# Main.net
KiCad netlist of a schematic drawn in Altium Designer
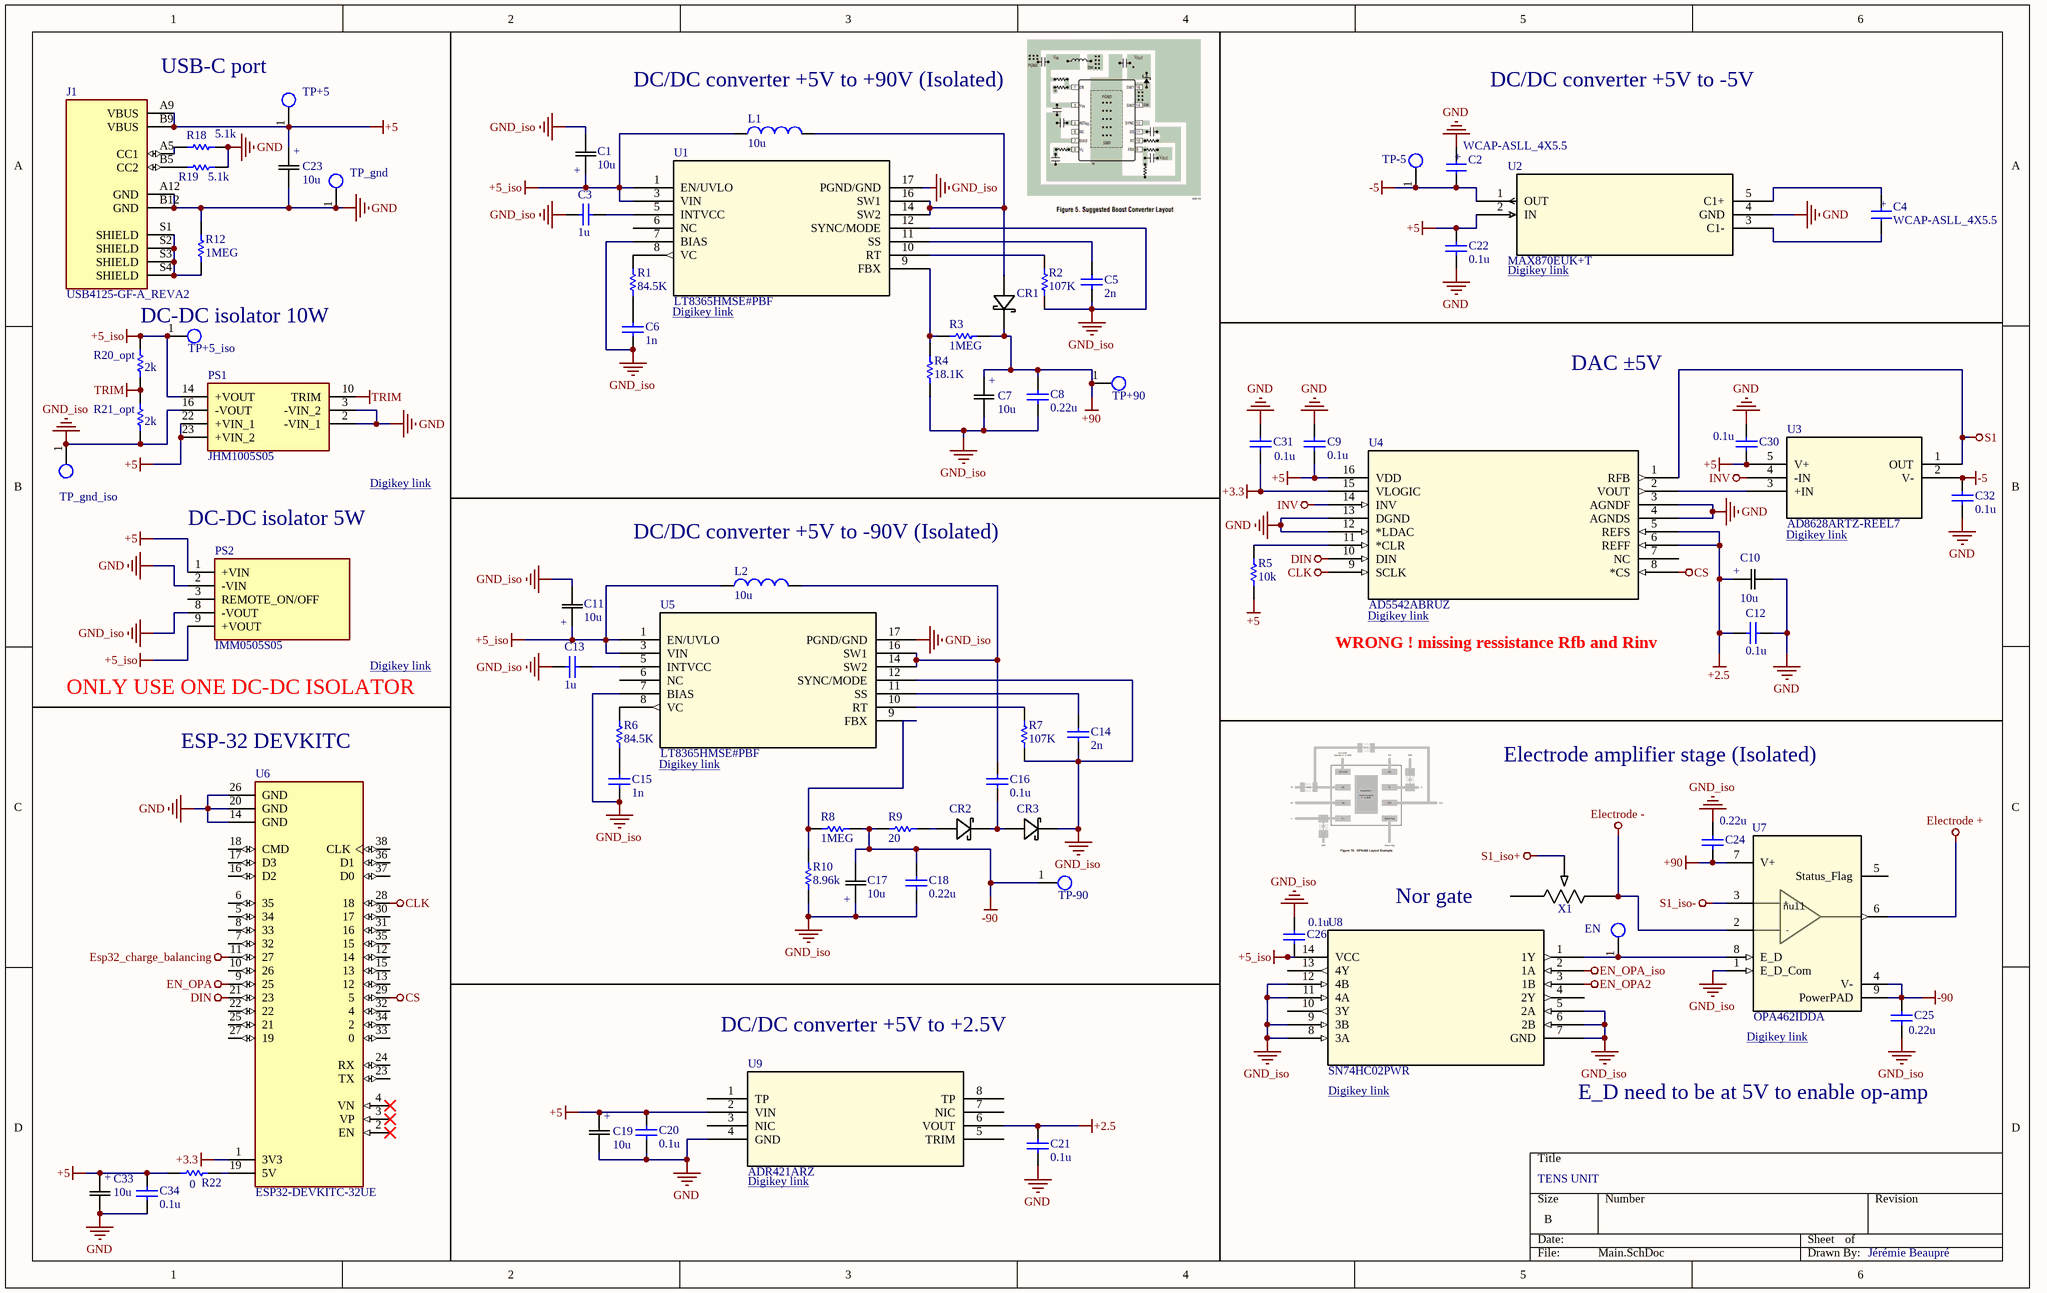
[diagram p0: Main.SchDoc]

(export (version "E")
  (design (tool "Eeschema 10.0.6"))
  (components
    (comp (ref "C1")
      (value "10u")
      (footprint "CAP_BX_10x20_RUB")
      (description "No Description Available")
      (fields
        (field (name "MANUFACTURER_PART_NUMBER") "450BXC10MEFC10X20")
        (field (name "COPYRIGHT") "Copyright (C) 2026 Ultra Librarian. All rights reserved.")
      )
      (libsource (lib "450BXC10MEFC10X20") (part "450BXC10MEFC10X20"))
    )
    (comp (ref "C2")
      (value "WCAP-ASLL_4X5.5")
      (footprint "WCAP-ASLL_4X5.5(DXL)")
      (fields
        (field (name "MF") "{'manufacturer': u'~{W}xfcrth Elektronik'}")
        (field (name "MP") "865060640001")
      )
      (libsource (lib "WCAP-ASLL_4X5.5") (part "WCAP-ASLL_4X5.5"))
    )
    (comp (ref "C3")
      (value "1u")
      (footprint "0805_AVX")
      (description "Capacitor")
      (libsource (lib "Simulation Generic Components") (part "Capacitor"))
    )
    (comp (ref "C4")
      (value "WCAP-ASLL_4X5.5")
      (footprint "WCAP-ASLL_4X5.5(DXL)")
      (fields
        (field (name "MF") "{'manufacturer': u'~{W}xfcrth Elektronik'}")
        (field (name "MP") "865060640001")
      )
      (libsource (lib "WCAP-ASLL_4X5.5") (part "WCAP-ASLL_4X5.5"))
    )
    (comp (ref "C5")
      (value "2n")
      (footprint "CAPC2012X75N")
      (description "Capacitor")
      (libsource (lib "Simulation Generic Components") (part "Capacitor"))
    )
    (comp (ref "C6")
      (value "1n")
      (footprint "CC0805N_YAG")
      (description "Capacitor")
      (libsource (lib "Simulation Generic Components") (part "Capacitor"))
    )
    (comp (ref "C7")
      (value "10u")
      (footprint "CAP_BX_10x20_RUB")
      (description "No Description Available")
      (fields
        (field (name "MANUFACTURER_PART_NUMBER") "450BXC10MEFC10X20")
        (field (name "COPYRIGHT") "Copyright (C) 2026 Ultra Librarian. All rights reserved.")
      )
      (libsource (lib "450BXC10MEFC10X20") (part "450BXC10MEFC10X20"))
    )
    (comp (ref "C8")
      (value "0.22u")
      (footprint "CAP_C3225X7R2E224K200AA")
      (description "Capacitor")
      (libsource (lib "Simulation Generic Components") (part "Capacitor"))
    )
    (comp (ref "C9")
      (value "0.1u")
      (footprint "CAPC2012X150N")
      (description "Capacitor")
      (libsource (lib "Simulation Generic Components") (part "Capacitor"))
    )
    (comp (ref "C10")
      (value "10u")
      (footprint "CAP_BX_10x20_RUB")
      (description "No Description Available")
      (fields
        (field (name "MANUFACTURER_PART_NUMBER") "450BXC10MEFC10X20")
        (field (name "COPYRIGHT") "Copyright (C) 2026 Ultra Librarian. All rights reserved.")
      )
      (libsource (lib "450BXC10MEFC10X20") (part "450BXC10MEFC10X20"))
    )
    (comp (ref "C11")
      (value "10u")
      (footprint "CAP_BX_10x20_RUB")
      (description "No Description Available")
      (fields
        (field (name "MANUFACTURER_PART_NUMBER") "450BXC10MEFC10X20")
        (field (name "COPYRIGHT") "Copyright (C) 2026 Ultra Librarian. All rights reserved.")
      )
      (libsource (lib "450BXC10MEFC10X20") (part "450BXC10MEFC10X20"))
    )
    (comp (ref "C12")
      (value "0.1u")
      (footprint "CAPC2012X150N")
      (description "Capacitor")
      (libsource (lib "Simulation Generic Components") (part "Capacitor"))
    )
    (comp (ref "C13")
      (value "1u")
      (footprint "0805_AVX")
      (description "Capacitor")
      (libsource (lib "Simulation Generic Components") (part "Capacitor"))
    )
    (comp (ref "C14")
      (value "2n")
      (footprint "CAPC2012X75N")
      (description "Capacitor")
      (libsource (lib "Simulation Generic Components") (part "Capacitor"))
    )
    (comp (ref "C15")
      (value "1n")
      (footprint "CC0805N_YAG")
      (description "Capacitor")
      (libsource (lib "Simulation Generic Components") (part "Capacitor"))
    )
    (comp (ref "C16")
      (value "0.1u")
      (footprint "CAPC2012X150N")
      (description "Capacitor")
      (libsource (lib "Simulation Generic Components") (part "Capacitor"))
    )
    (comp (ref "C17")
      (value "10u")
      (footprint "CAP_BX_10x20_RUB")
      (description "No Description Available")
      (fields
        (field (name "MANUFACTURER_PART_NUMBER") "450BXC10MEFC10X20")
        (field (name "COPYRIGHT") "Copyright (C) 2026 Ultra Librarian. All rights reserved.")
      )
      (libsource (lib "450BXC10MEFC10X20") (part "450BXC10MEFC10X20"))
    )
    (comp (ref "C18")
      (value "0.22u")
      (footprint "CAP_C3225X7R2E224K200AA")
      (description "Capacitor")
      (libsource (lib "Simulation Generic Components") (part "Capacitor"))
    )
    (comp (ref "C19")
      (value "10u")
      (footprint "CAP_BX_10x20_RUB")
      (description "No Description Available")
      (fields
        (field (name "MANUFACTURER_PART_NUMBER") "450BXC10MEFC10X20")
        (field (name "COPYRIGHT") "Copyright (C) 2026 Ultra Librarian. All rights reserved.")
      )
      (libsource (lib "450BXC10MEFC10X20") (part "450BXC10MEFC10X20"))
    )
    (comp (ref "C20")
      (value "0.1u")
      (footprint "CAPC2012X150N")
      (description "Capacitor")
      (libsource (lib "Simulation Generic Components") (part "Capacitor"))
    )
    (comp (ref "C21")
      (value "0.1u")
      (footprint "CAPC2012X150N")
      (description "Capacitor")
      (libsource (lib "Simulation Generic Components") (part "Capacitor"))
    )
    (comp (ref "C22")
      (value "0.1u")
      (footprint "CAPC2012X150N")
      (description "Capacitor")
      (libsource (lib "Simulation Generic Components") (part "Capacitor"))
    )
    (comp (ref "C23")
      (value "10u")
      (footprint "CAP_BX_10x20_RUB")
      (description "No Description Available")
      (fields
        (field (name "MANUFACTURER_PART_NUMBER") "450BXC10MEFC10X20")
        (field (name "COPYRIGHT") "Copyright (C) 2026 Ultra Librarian. All rights reserved.")
      )
      (libsource (lib "450BXC10MEFC10X20") (part "450BXC10MEFC10X20"))
    )
    (comp (ref "C24")
      (value "0.22u")
      (footprint "CAP_C3225X7R2E224K200AA")
      (description "Capacitor")
      (libsource (lib "Simulation Generic Components") (part "Capacitor"))
    )
    (comp (ref "C25")
      (value "0.22u")
      (footprint "CAP_C3225X7R2E224K200AA")
      (description "Capacitor")
      (libsource (lib "Simulation Generic Components") (part "Capacitor"))
    )
    (comp (ref "C26")
      (value "0.1u")
      (footprint "CAPC2012X150N")
      (description "Capacitor")
      (libsource (lib "Simulation Generic Components") (part "Capacitor"))
    )
    (comp (ref "C30")
      (value "0.1u")
      (footprint "CAPC2012X150N")
      (description "Capacitor")
      (libsource (lib "Simulation Generic Components") (part "Capacitor"))
    )
    (comp (ref "C31")
      (value "0.1u")
      (footprint "CAPC2012X150N")
      (description "Capacitor")
      (libsource (lib "Simulation Generic Components") (part "Capacitor"))
    )
    (comp (ref "C32")
      (value "0.1u")
      (footprint "CAPC2012X150N")
      (description "Capacitor")
      (libsource (lib "Simulation Generic Components") (part "Capacitor"))
    )
    (comp (ref "C33")
      (value "10u")
      (footprint "CAP_BX_10x20_RUB")
      (description "No Description Available")
      (fields
        (field (name "MANUFACTURER_PART_NUMBER") "450BXC10MEFC10X20")
        (field (name "COPYRIGHT") "Copyright (C) 2026 Ultra Librarian. All rights reserved.")
      )
      (libsource (lib "450BXC10MEFC10X20") (part "450BXC10MEFC10X20"))
    )
    (comp (ref "C34")
      (value "0.1u")
      (footprint "CAPC2012X150N")
      (description "Capacitor")
      (libsource (lib "Simulation Generic Components") (part "Capacitor"))
    )
    (comp (ref "CR1")
      (value "SK220ATR")
      (footprint "DIODE_SK220ATR_SMC-M")
      (description "No Description Available")
      (fields (field (name "COPYRIGHT") "Copyright (C) 2026 Ultra Librarian. All rights reserved."))
      (libsource (lib "SK220ATR") (part "SK220ATR"))
    )
    (comp (ref "CR2")
      (value "SK220ATR")
      (footprint "DIODE_SK220ATR_SMC-M")
      (description "No Description Available")
      (fields (field (name "COPYRIGHT") "Copyright (C) 2026 Ultra Librarian. All rights reserved."))
      (libsource (lib "SK220ATR") (part "SK220ATR"))
    )
    (comp (ref "CR3")
      (value "SK220ATR")
      (footprint "DIODE_SK220ATR_SMC-M")
      (description "No Description Available")
      (fields (field (name "COPYRIGHT") "Copyright (C) 2026 Ultra Librarian. All rights reserved."))
      (libsource (lib "SK220ATR") (part "SK220ATR"))
    )
    (comp (ref "EN")
      (value "Testpoint_1")
      (footprint "Testpoint1")
      (libsource (lib "My_lib") (part "Testpoint_1"))
    )
    (comp (ref "J1")
      (value "USB4125-GF-A_REVA2")
      (footprint "GCT_USB4125-GF-A_REVA2")
      (libsource (lib "USB4125-GF-A_REVA2") (part "USB4125-GF-A_REVA2"))
    )
    (comp (ref "L1")
      (value "10u")
      (footprint "DR73")
      (description "Inductor")
      (libsource (lib "Simulation Generic Components") (part "Inductor"))
    )
    (comp (ref "L2")
      (value "10u")
      (footprint "DR73")
      (description "Inductor")
      (libsource (lib "Simulation Generic Components") (part "Inductor"))
    )
    (comp (ref "PS1")
      (value "JHM1005S05")
      (footprint "SamacSys:JHM1005S05")
      (description "Power Supply")
      (fields (field (name "MOUSER PART NUMBER") "209-JHM1005S05"))
      (libsource (lib "*") (part "JHM1005S05"))
    )
    (comp (ref "PS2")
      (value "IMM0505S05")
      (footprint "SamacSys:IMM0505S05")
      (description "Power Supply")
      (fields (field (name "MOUSER PART NUMBER") "209-IMM0505S05"))
      (libsource (lib "*") (part "IMM0505S05"))
    )
    (comp (ref "R1")
      (value "84.5K")
      (footprint "Resistor_0805-M")
      (description "Resistor")
      (libsource (lib "Simulation Generic Components") (part "Resistor"))
    )
    (comp (ref "R2")
      (value "107K")
      (footprint "Resistor_0805-M")
      (description "Resistor")
      (libsource (lib "Simulation Generic Components") (part "Resistor"))
    )
    (comp (ref "R3")
      (value "1MEG")
      (footprint "Resistor_0805-M")
      (description "Resistor")
      (libsource (lib "Simulation Generic Components") (part "Resistor"))
    )
    (comp (ref "R4")
      (value "18.1K")
      (footprint "Resistor_0805-M")
      (description "Resistor")
      (libsource (lib "Simulation Generic Components") (part "Resistor"))
    )
    (comp (ref "R5")
      (value "10k")
      (footprint "Resistor_0805-M")
      (description "Resistor")
      (libsource (lib "Simulation Generic Components") (part "Resistor"))
    )
    (comp (ref "R6")
      (value "84.5K")
      (footprint "Resistor_0805-M")
      (description "Resistor")
      (libsource (lib "Simulation Generic Components") (part "Resistor"))
    )
    (comp (ref "R7")
      (value "107K")
      (footprint "Resistor_0805-M")
      (description "Resistor")
      (libsource (lib "Simulation Generic Components") (part "Resistor"))
    )
    (comp (ref "R8")
      (value "1MEG")
      (footprint "Resistor_0805-M")
      (description "Resistor")
      (libsource (lib "Simulation Generic Components") (part "Resistor"))
    )
    (comp (ref "R9")
      (value "20")
      (footprint "Resistor_0805-M")
      (description "Resistor")
      (libsource (lib "Simulation Generic Components") (part "Resistor"))
    )
    (comp (ref "R10")
      (value "8.96k")
      (footprint "Resistor_0805-M")
      (description "Resistor")
      (libsource (lib "Simulation Generic Components") (part "Resistor"))
    )
    (comp (ref "R12")
      (value "1MEG")
      (footprint "Resistor_0805-M")
      (description "Resistor")
      (libsource (lib "Simulation Generic Components") (part "Resistor"))
    )
    (comp (ref "R18")
      (value "5.1k")
      (footprint "Resistor_0805-M")
      (description "Resistor")
      (libsource (lib "Simulation Generic Components") (part "Resistor"))
    )
    (comp (ref "R19")
      (value "5.1k")
      (footprint "Resistor_0805-M")
      (description "Resistor")
      (libsource (lib "Simulation Generic Components") (part "Resistor"))
    )
    (comp (ref "R20_opt")
      (value "2k")
      (footprint "Resistor_0805-M")
      (description "Resistor")
      (libsource (lib "Simulation Generic Components") (part "Resistor"))
    )
    (comp (ref "R21_opt")
      (value "2k")
      (footprint "Resistor_0805-M")
      (description "Resistor")
      (libsource (lib "Simulation Generic Components") (part "Resistor"))
    )
    (comp (ref "R22")
      (value "0")
      (footprint "Resistor_0805-M")
      (description "Resistor")
      (libsource (lib "Simulation Generic Components") (part "Resistor"))
    )
    (comp (ref "TP+5")
      (value "Testpoint_1")
      (footprint "Testpoint1")
      (libsource (lib "My_lib") (part "Testpoint_1"))
    )
    (comp (ref "TP+5_iso")
      (value "Testpoint_1")
      (footprint "Testpoint1")
      (libsource (lib "My_lib") (part "Testpoint_1"))
    )
    (comp (ref "TP+90")
      (value "Testpoint_1")
      (footprint "Testpoint1")
      (libsource (lib "My_lib") (part "Testpoint_1"))
    )
    (comp (ref "TP-5")
      (value "Testpoint_1")
      (footprint "Testpoint1")
      (libsource (lib "My_lib") (part "Testpoint_1"))
    )
    (comp (ref "TP-90")
      (value "Testpoint_1")
      (footprint "Testpoint1")
      (libsource (lib "My_lib") (part "Testpoint_1"))
    )
    (comp (ref "TP_gnd")
      (value "Testpoint_1")
      (footprint "Testpoint1")
      (libsource (lib "My_lib") (part "Testpoint_1"))
    )
    (comp (ref "TP_gnd_iso")
      (value "Testpoint_1")
      (footprint "Testpoint1")
      (libsource (lib "My_lib") (part "Testpoint_1"))
    )
    (comp (ref "U1")
      (value "LT8365HMSE#PBF")
      (footprint "05-08-1871_ADI")
      (description "Low IQ Boost/SEPIC/Inverting Converter with 1.5A, 150V SwitchÂ")
      (fields (field (name "COPYRIGHT") "Copyright (C) 2025 Ultra Librarian. All rights reserved."))
      (libsource (lib "LT8365HMSEPBF") (part "LT8365HMSEPBF"))
    )
    (comp (ref "U2")
      (value "MAX870EUK+T")
      (footprint "21-0057F_MXM")
      (description "Switched-Capacitor Voltage Inverters")
      (fields (field (name "COPYRIGHT") "Copyright (C) 2026 Ultra Librarian. All rights reserved."))
      (libsource (lib "MAX870EUK&plus_T") (part "MAX870EUK+T"))
    )
    (comp (ref "U3")
      (value "AD8628ARTZ-REEL7")
      (footprint "RJ_5_ADI")
      (description "Zero-Drift, Single-Supply, Rail-to-Rail Input/Output Operational Amplifier")
      (fields (field (name "COPYRIGHT") "Copyright (C) 2025 Ultra Librarian. All rights reserved."))
      (libsource (lib "AD8628ARTZ-REEL7") (part "AD8628ARTZ-REEL7"))
    )
    (comp (ref "U4")
      (value "AD5542ABRUZ")
      (footprint "RU_16_ADI")
      (fields (field (name "COPYRIGHT") "Copyright (C) 2026 Ultra Librarian. All rights reserved."))
      (libsource (lib "AD5542ABRUZ") (part "AD5542ABRUZ"))
    )
    (comp (ref "U5")
      (value "LT8365HMSE#PBF")
      (footprint "05-08-1871_ADI")
      (description "Low IQ Boost/SEPIC/Inverting Converter with 1.5A, 150V SwitchÂ")
      (fields (field (name "COPYRIGHT") "Copyright (C) 2025 Ultra Librarian. All rights reserved."))
      (libsource (lib "LT8365HMSEPBF") (part "LT8365HMSEPBF"))
    )
    (comp (ref "U6")
      (value "ESP32-DEVKITC-32UE")
      (footprint "ESPRESSIF_ESP32-DEVKITC-32UE")
      (fields (field (name "MF") "Espressif Systems"))
      (libsource (lib "ESP32-DEVKITC-32UE") (part "ESP32-DEVKITC-32UE"))
    )
    (comp (ref "U7")
      (value "OPA462IDDA")
      (footprint "DDA0008J-IPC_A")
      (fields (field (name "COPYRIGHT") "Copyright (C) 2026 Ultra Librarian. All rights reserved."))
      (libsource (lib "OPA462IDDA") (part "OPA462IDDA"))
    )
    (comp (ref "U8")
      (value "SN74HC02PWR")
      (footprint "PW14")
      (description "4-ch, 2-input, 2-V to 6-V 5.2 mA drive strength NOR gate 14-TSSOP -40 to 85")
      (fields (field (name "COPYRIGHT") "Copyright (C) 2026 Ultra Librarian. All rights reserved."))
      (libsource (lib "SN74HC02PWR") (part "SN74HC02PWR"))
    )
    (comp (ref "U9")
      (value "ADR421ARZ")
      (footprint "R_8_ADI")
      (description "Ultraprecision, Low Noise, 2.500 V XFETÂ® Voltage References")
      (fields (field (name "COPYRIGHT") "Copyright (C) 2026 Ultra Librarian. All rights reserved."))
      (libsource (lib "ADR421ARZ") (part "ADR421ARZ"))
    )
    (comp (ref "X1")
      (value "PV36W102C01B00")
      (footprint "POT_PV36W_MUR")
      (description "No Description Available")
      (fields (field (name "COPYRIGHT") "Copyright (C) 2026 Ultra Librarian. All rights reserved."))
      (libsource (lib "PV36W102C01B00") (part "PV36W102C01B00"))
    )
  )
  (nets
    (net (code "1") (name "+2.5") (class "Default")
      (node (ref "C10") (pin "1") (pinfunction "+_1") (pintype "passive"))
      (node (ref "C12") (pin "2") (pinfunction "2_2") (pintype "passive"))
      (node (ref "C21") (pin "2") (pinfunction "2_2") (pintype "passive"))
      (node (ref "U4") (pin "5") (pinfunction "REFS_5") (pintype "input"))
      (node (ref "U4") (pin "6") (pinfunction "REFF_6") (pintype "input"))
      (node (ref "U9") (pin "6") (pinfunction "VOUT_6") (pintype "power_in"))
    )
    (net (code "2") (name "+3.3") (class "Default")
      (node (ref "C31") (pin "2") (pinfunction "2_2") (pintype "passive"))
      (node (ref "U4") (pin "15") (pinfunction "VLOGIC_15") (pintype "power_in"))
      (node (ref "U6") (pin "1") (pinfunction "3V3_1") (pintype "power_in"))
    )
    (net (code "3") (name "+5") (class "Default")
      (node (ref "C19") (pin "1") (pinfunction "+_1") (pintype "passive"))
      (node (ref "C20") (pin "2") (pinfunction "2_2") (pintype "passive"))
      (node (ref "C22") (pin "1") (pinfunction "1_1") (pintype "passive"))
      (node (ref "C23") (pin "1") (pinfunction "+_1") (pintype "passive"))
      (node (ref "C30") (pin "2") (pinfunction "2_2") (pintype "passive"))
      (node (ref "C33") (pin "1") (pinfunction "+_1") (pintype "passive"))
      (node (ref "C34") (pin "2") (pinfunction "2_2") (pintype "passive"))
      (node (ref "C9") (pin "2") (pinfunction "2_2") (pintype "passive"))
      (node (ref "J1") (pin "A9") (pinfunction "VBUS_A9") (pintype "power_in"))
      (node (ref "J1") (pin "B9") (pinfunction "VBUS_B9") (pintype "power_in"))
      (node (ref "PS1") (pin "22") (pinfunction "+VIN_1_22") (pintype "passive"))
      (node (ref "PS1") (pin "23") (pinfunction "+VIN_2_23") (pintype "passive"))
      (node (ref "PS2") (pin "1") (pinfunction "+VIN_1") (pintype "passive"))
      (node (ref "R22") (pin "2") (pinfunction "2_2") (pintype "passive"))
      (node (ref "R5") (pin "1") (pinfunction "1_1") (pintype "passive"))
      (node (ref "TP+5") (pin "1") (pinfunction "P1_1") (pintype "passive"))
      (node (ref "U2") (pin "2") (pinfunction "IN_2") (pintype "input"))
      (node (ref "U3") (pin "5") (pinfunction "V+_5") (pintype "power_in"))
      (node (ref "U4") (pin "16") (pinfunction "VDD_16") (pintype "power_in"))
      (node (ref "U9") (pin "2") (pinfunction "VIN_2") (pintype "passive"))
    )
    (net (code "4") (name "+5_iso") (class "Default")
      (node (ref "C1") (pin "1") (pinfunction "+_1") (pintype "passive"))
      (node (ref "C11") (pin "1") (pinfunction "+_1") (pintype "passive"))
      (node (ref "C26") (pin "1") (pinfunction "1_1") (pintype "passive"))
      (node (ref "L1") (pin "1") (pinfunction "1_1") (pintype "passive"))
      (node (ref "L2") (pin "1") (pinfunction "1_1") (pintype "passive"))
      (node (ref "PS1") (pin "14") (pinfunction "+VOUT_14") (pintype "passive"))
      (node (ref "PS2") (pin "9") (pinfunction "+VOUT_9") (pintype "passive"))
      (node (ref "R20_opt") (pin "1") (pinfunction "1_1") (pintype "passive"))
      (node (ref "TP+5_iso") (pin "1") (pinfunction "P1_1") (pintype "passive"))
      (node (ref "U1") (pin "1") (pinfunction "EN/UVLO_1") (pintype "passive"))
      (node (ref "U1") (pin "3") (pinfunction "VIN_3") (pintype "power_in"))
      (node (ref "U5") (pin "1") (pinfunction "EN/UVLO_1") (pintype "passive"))
      (node (ref "U5") (pin "3") (pinfunction "VIN_3") (pintype "power_in"))
      (node (ref "U8") (pin "14") (pinfunction "VCC_14") (pintype "power_in"))
    )
    (net (code "5") (name "+90") (class "Default")
      (node (ref "C24") (pin "2") (pinfunction "2_2") (pintype "passive"))
      (node (ref "C7") (pin "1") (pinfunction "+_1") (pintype "passive"))
      (node (ref "C8") (pin "2") (pinfunction "2_2") (pintype "passive"))
      (node (ref "CR1") (pin "1") (pinfunction "1_1") (pintype "passive"))
      (node (ref "R3") (pin "2") (pinfunction "2_2") (pintype "passive"))
      (node (ref "TP+90") (pin "1") (pinfunction "P1_1") (pintype "passive"))
      (node (ref "U7") (pin "7") (pinfunction "V+_7") (pintype "power_in"))
    )
    (net (code "6") (name "-5") (class "Default")
      (node (ref "C2") (pin "2") (pinfunction "NEG_2") (pintype "passive"))
      (node (ref "C32") (pin "2") (pinfunction "2_2") (pintype "passive"))
      (node (ref "TP-5") (pin "1") (pinfunction "P1_1") (pintype "passive"))
      (node (ref "U2") (pin "1") (pinfunction "OUT_1") (pintype "power_in"))
      (node (ref "U3") (pin "2") (pinfunction "V-_2") (pintype "power_in"))
    )
    (net (code "7") (name "-90") (class "Default")
      (node (ref "C17") (pin "2") (pinfunction "2_2") (pintype "passive"))
      (node (ref "C18") (pin "2") (pinfunction "2_2") (pintype "passive"))
      (node (ref "C25") (pin "1") (pinfunction "1_1") (pintype "passive"))
      (node (ref "R8") (pin "1") (pinfunction "1_1") (pintype "passive"))
      (node (ref "R9") (pin "2") (pinfunction "2_2") (pintype "passive"))
      (node (ref "TP-90") (pin "1") (pinfunction "P1_1") (pintype "passive"))
      (node (ref "U7") (pin "4") (pinfunction "V-_4") (pintype "power_in"))
      (node (ref "U7") (pin "9") (pinfunction "PowerPAD_9") (pintype "power_in"))
    )
    (net (code "8") (name "CLK") (class "Default")
      (node (ref "U4") (pin "9") (pinfunction "SCLK_9") (pintype "input"))
      (node (ref "U6") (pin "28") (pinfunction "18_28") (pintype "bidirectional"))
    )
    (net (code "9") (name "CS") (class "Default")
      (node (ref "U4") (pin "8") (pinfunction "*CS_8") (pintype "input"))
      (node (ref "U6") (pin "29") (pinfunction "5_29") (pintype "bidirectional"))
    )
    (net (code "10") (name "DIN") (class "Default")
      (node (ref "U4") (pin "10") (pinfunction "DIN_10") (pintype "input"))
      (node (ref "U6") (pin "21") (pinfunction "23_21") (pintype "bidirectional"))
    )
    (net (code "11") (name "EN_OPA") (class "Default")
      (node (ref "U6") (pin "9") (pinfunction "25_9") (pintype "bidirectional"))
    )
    (net (code "12") (name "EN_OPA2") (class "Default")
      (node (ref "U8") (pin "3") (pinfunction "1B_3") (pintype "input"))
    )
    (net (code "13") (name "EN_OPA_iso") (class "Default")
      (node (ref "U8") (pin "2") (pinfunction "1A_2") (pintype "input"))
    )
    (net (code "14") (name "Electrode +") (class "Default")
      (node (ref "U7") (pin "6") (pinfunction "OUT_6") (pintype "output"))
    )
    (net (code "15") (name "Electrode -") (class "Default")
      (node (ref "U7") (pin "2") (pinfunction "-IN_2") (pintype "tri_state"))
      (node (ref "X1") (pin "3") (pinfunction "3_3") (pintype "passive"))
    )
    (net (code "16") (name "Esp32_charge_balancing") (class "Default")
      (node (ref "U6") (pin "11") (pinfunction "27_11") (pintype "bidirectional"))
    )
    (net (code "17") (name "GND") (class "Default")
      (node (ref "C10") (pin "2") (pinfunction "2_2") (pintype "passive"))
      (node (ref "C12") (pin "1") (pinfunction "1_1") (pintype "passive"))
      (node (ref "C19") (pin "2") (pinfunction "2_2") (pintype "passive"))
      (node (ref "C2") (pin "1") (pinfunction "POS_1") (pintype "passive"))
      (node (ref "C20") (pin "1") (pinfunction "1_1") (pintype "passive"))
      (node (ref "C21") (pin "1") (pinfunction "1_1") (pintype "passive"))
      (node (ref "C22") (pin "2") (pinfunction "2_2") (pintype "passive"))
      (node (ref "C23") (pin "2") (pinfunction "2_2") (pintype "passive"))
      (node (ref "C30") (pin "1") (pinfunction "1_1") (pintype "passive"))
      (node (ref "C31") (pin "1") (pinfunction "1_1") (pintype "passive"))
      (node (ref "C32") (pin "1") (pinfunction "1_1") (pintype "passive"))
      (node (ref "C33") (pin "2") (pinfunction "2_2") (pintype "passive"))
      (node (ref "C34") (pin "1") (pinfunction "1_1") (pintype "passive"))
      (node (ref "C9") (pin "1") (pinfunction "1_1") (pintype "passive"))
      (node (ref "J1") (pin "A12") (pinfunction "GND_A12") (pintype "power_in"))
      (node (ref "J1") (pin "B12") (pinfunction "GND_B12") (pintype "power_in"))
      (node (ref "PS1") (pin "2") (pinfunction "-VIN_1_2") (pintype "passive"))
      (node (ref "PS1") (pin "3") (pinfunction "-VIN_2_3") (pintype "passive"))
      (node (ref "PS2") (pin "2") (pinfunction "-VIN_2") (pintype "passive"))
      (node (ref "R12") (pin "2") (pinfunction "2_2") (pintype "passive"))
      (node (ref "R18") (pin "1") (pinfunction "1_1") (pintype "passive"))
      (node (ref "R19") (pin "1") (pinfunction "1_1") (pintype "passive"))
      (node (ref "TP_gnd") (pin "1") (pinfunction "P1_1") (pintype "passive"))
      (node (ref "U2") (pin "4") (pinfunction "GND_4") (pintype "power_in"))
      (node (ref "U4") (pin "12") (pinfunction "*LDAC_12") (pintype "input"))
      (node (ref "U4") (pin "13") (pinfunction "DGND_13") (pintype "power_in"))
      (node (ref "U4") (pin "3") (pinfunction "AGNDF_3") (pintype "power_in"))
      (node (ref "U4") (pin "4") (pinfunction "AGNDS_4") (pintype "power_in"))
      (node (ref "U6") (pin "14") (pinfunction "GND_14") (pintype "power_in"))
      (node (ref "U6") (pin "20") (pinfunction "GND_20") (pintype "power_in"))
      (node (ref "U6") (pin "26") (pinfunction "GND_26") (pintype "power_in"))
      (node (ref "U9") (pin "4") (pinfunction "GND_4") (pintype "passive"))
    )
    (net (code "18") (name "GND_iso") (class "Default")
      (node (ref "C1") (pin "2") (pinfunction "2_2") (pintype "passive"))
      (node (ref "C11") (pin "2") (pinfunction "2_2") (pintype "passive"))
      (node (ref "C13") (pin "2") (pinfunction "2_2") (pintype "passive"))
      (node (ref "C14") (pin "1") (pinfunction "1_1") (pintype "passive"))
      (node (ref "C15") (pin "1") (pinfunction "1_1") (pintype "passive"))
      (node (ref "C17") (pin "1") (pinfunction "+_1") (pintype "passive"))
      (node (ref "C18") (pin "1") (pinfunction "1_1") (pintype "passive"))
      (node (ref "C24") (pin "1") (pinfunction "1_1") (pintype "passive"))
      (node (ref "C25") (pin "2") (pinfunction "2_2") (pintype "passive"))
      (node (ref "C26") (pin "2") (pinfunction "2_2") (pintype "passive"))
      (node (ref "C3") (pin "2") (pinfunction "2_2") (pintype "passive"))
      (node (ref "C5") (pin "1") (pinfunction "1_1") (pintype "passive"))
      (node (ref "C6") (pin "1") (pinfunction "1_1") (pintype "passive"))
      (node (ref "C7") (pin "2") (pinfunction "2_2") (pintype "passive"))
      (node (ref "C8") (pin "1") (pinfunction "1_1") (pintype "passive"))
      (node (ref "CR3") (pin "1") (pinfunction "1_1") (pintype "passive"))
      (node (ref "PS1") (pin "16") (pinfunction "-VOUT_16") (pintype "passive"))
      (node (ref "PS2") (pin "8") (pinfunction "-VOUT_8") (pintype "passive"))
      (node (ref "R10") (pin "2") (pinfunction "2_2") (pintype "passive"))
      (node (ref "R2") (pin "1") (pinfunction "1_1") (pintype "passive"))
      (node (ref "R21_opt") (pin "2") (pinfunction "2_2") (pintype "passive"))
      (node (ref "R4") (pin "2") (pinfunction "2_2") (pintype "passive"))
      (node (ref "R7") (pin "1") (pinfunction "1_1") (pintype "passive"))
      (node (ref "TP_gnd_iso") (pin "1") (pinfunction "P1_1") (pintype "passive"))
      (node (ref "U1") (pin "12") (pinfunction "SYNC/MODE_12") (pintype "passive"))
      (node (ref "U1") (pin "17") (pinfunction "PGND/GND_17") (pintype "power_in"))
      (node (ref "U1") (pin "7") (pinfunction "BIAS_7") (pintype "power_in"))
      (node (ref "U5") (pin "12") (pinfunction "SYNC/MODE_12") (pintype "passive"))
      (node (ref "U5") (pin "17") (pinfunction "PGND/GND_17") (pintype "power_in"))
      (node (ref "U5") (pin "7") (pinfunction "BIAS_7") (pintype "power_in"))
      (node (ref "U7") (pin "1") (pinfunction "E_D_Com_1") (pintype "input"))
      (node (ref "U8") (pin "11") (pinfunction "4A_11") (pintype "input"))
      (node (ref "U8") (pin "12") (pinfunction "4B_12") (pintype "input"))
      (node (ref "U8") (pin "5") (pinfunction "2A_5") (pintype "input"))
      (node (ref "U8") (pin "6") (pinfunction "2B_6") (pintype "input"))
      (node (ref "U8") (pin "7") (pinfunction "GND_7") (pintype "power_in"))
      (node (ref "U8") (pin "8") (pinfunction "3A_8") (pintype "input"))
      (node (ref "U8") (pin "9") (pinfunction "3B_9") (pintype "input"))
    )
    (net (code "19") (name "INV") (class "Default")
      (node (ref "U3") (pin "4") (pinfunction "-IN_4") (pintype "passive"))
      (node (ref "U4") (pin "14") (pinfunction "INV_14") (pintype "input"))
    )
    (net (code "20") (name "Net-(C4-NEG)") (class "Default")
      (node (ref "C4") (pin "2") (pinfunction "NEG_2") (pintype "passive"))
      (node (ref "U2") (pin "3") (pinfunction "C1-_3") (pintype "passive"))
    )
    (net (code "21") (name "Net-(C4-POS)") (class "Default")
      (node (ref "C4") (pin "1") (pinfunction "POS_1") (pintype "passive"))
      (node (ref "U2") (pin "5") (pinfunction "C1+_5") (pintype "passive"))
    )
    (net (code "22") (name "Net-(C6-Pad2)") (class "Default")
      (node (ref "C6") (pin "2") (pinfunction "2_2") (pintype "passive"))
      (node (ref "R1") (pin "1") (pinfunction "1_1") (pintype "passive"))
    )
    (net (code "23") (name "Net-(C15-Pad2)") (class "Default")
      (node (ref "C15") (pin "2") (pinfunction "2_2") (pintype "passive"))
      (node (ref "R6") (pin "1") (pinfunction "1_1") (pintype "passive"))
    )
    (net (code "24") (name "Net-(C16-Pad1)") (class "Default")
      (node (ref "C16") (pin "1") (pinfunction "1_1") (pintype "passive"))
      (node (ref "CR2") (pin "1") (pinfunction "1_1") (pintype "passive"))
      (node (ref "CR3") (pin "2") (pinfunction "2_2") (pintype "passive"))
    )
    (net (code "25") (name "Net-(CR2-Pad2)") (class "Default")
      (node (ref "CR2") (pin "2") (pinfunction "2_2") (pintype "passive"))
      (node (ref "R9") (pin "1") (pinfunction "1_1") (pintype "passive"))
    )
    (net (code "26") (name "Net-(EN-P1)") (class "Default")
      (node (ref "EN") (pin "1") (pinfunction "P1_1") (pintype "passive"))
      (node (ref "U7") (pin "8") (pinfunction "E_D_8") (pintype "input"))
      (node (ref "U8") (pin "1") (pinfunction "1Y_1") (pintype "output"))
    )
    (net (code "27") (name "Net-(J1-CC1)") (class "Default")
      (node (ref "J1") (pin "A5") (pinfunction "CC1_A5") (pintype "bidirectional"))
      (node (ref "R18") (pin "2") (pinfunction "2_2") (pintype "passive"))
    )
    (net (code "28") (name "Net-(J1-CC2)") (class "Default")
      (node (ref "J1") (pin "B5") (pinfunction "CC2_B5") (pintype "bidirectional"))
      (node (ref "R19") (pin "2") (pinfunction "2_2") (pintype "passive"))
    )
    (net (code "29") (name "Net-(J1-SHIELD-PadS1)") (class "Default")
      (node (ref "J1") (pin "S1") (pinfunction "SHIELD_S1") (pintype "passive"))
      (node (ref "J1") (pin "S2") (pinfunction "SHIELD_S2") (pintype "passive"))
      (node (ref "J1") (pin "S3") (pinfunction "SHIELD_S3") (pintype "passive"))
      (node (ref "J1") (pin "S4") (pinfunction "SHIELD_S4") (pintype "passive"))
      (node (ref "R12") (pin "1") (pinfunction "1_1") (pintype "passive"))
    )
    (net (code "30") (name "Net-(U1-FBX)") (class "Default")
      (node (ref "R3") (pin "1") (pinfunction "1_1") (pintype "passive"))
      (node (ref "R4") (pin "1") (pinfunction "1_1") (pintype "passive"))
      (node (ref "U1") (pin "9") (pinfunction "FBX_9") (pintype "passive"))
    )
    (net (code "31") (name "Net-(U1-INTVCC)") (class "Default")
      (node (ref "C3") (pin "1") (pinfunction "1_1") (pintype "passive"))
      (node (ref "U1") (pin "5") (pinfunction "INTVCC_5") (pintype "power_in"))
    )
    (net (code "32") (name "Net-(U1-RT)") (class "Default")
      (node (ref "R2") (pin "2") (pinfunction "2_2") (pintype "passive"))
      (node (ref "U1") (pin "10") (pinfunction "RT_10") (pintype "passive"))
    )
    (net (code "33") (name "Net-(U1-SS)") (class "Default")
      (node (ref "C5") (pin "2") (pinfunction "2_2") (pintype "passive"))
      (node (ref "U1") (pin "11") (pinfunction "SS_11") (pintype "passive"))
    )
    (net (code "34") (name "Net-(U1-SW1)") (class "Default")
      (node (ref "CR1") (pin "2") (pinfunction "2_2") (pintype "passive"))
      (node (ref "L1") (pin "2") (pinfunction "2_2") (pintype "passive"))
      (node (ref "U1") (pin "14") (pinfunction "SW2_14") (pintype "power_in"))
      (node (ref "U1") (pin "16") (pinfunction "SW1_16") (pintype "power_in"))
    )
    (net (code "35") (name "Net-(U1-VC)") (class "Default")
      (node (ref "R1") (pin "2") (pinfunction "2_2") (pintype "passive"))
      (node (ref "U1") (pin "8") (pinfunction "VC_8") (pintype "output"))
    )
    (net (code "36") (name "Net-(U3-+IN)") (class "Default")
      (node (ref "U3") (pin "3") (pinfunction "+IN_3") (pintype "passive"))
      (node (ref "U4") (pin "2") (pinfunction "VOUT_2") (pintype "output"))
    )
    (net (code "37") (name "Net-(U4-*CLR)") (class "Default")
      (node (ref "R5") (pin "2") (pinfunction "2_2") (pintype "passive"))
      (node (ref "U4") (pin "11") (pinfunction "*CLR_11") (pintype "input"))
    )
    (net (code "38") (name "Net-(U5-FBX)") (class "Default")
      (node (ref "R10") (pin "1") (pinfunction "1_1") (pintype "passive"))
      (node (ref "R8") (pin "2") (pinfunction "2_2") (pintype "passive"))
      (node (ref "U5") (pin "9") (pinfunction "FBX_9") (pintype "passive"))
    )
    (net (code "39") (name "Net-(U5-INTVCC)") (class "Default")
      (node (ref "C13") (pin "1") (pinfunction "1_1") (pintype "passive"))
      (node (ref "U5") (pin "5") (pinfunction "INTVCC_5") (pintype "power_in"))
    )
    (net (code "40") (name "Net-(U5-RT)") (class "Default")
      (node (ref "R7") (pin "2") (pinfunction "2_2") (pintype "passive"))
      (node (ref "U5") (pin "10") (pinfunction "RT_10") (pintype "passive"))
    )
    (net (code "41") (name "Net-(U5-SS)") (class "Default")
      (node (ref "C14") (pin "2") (pinfunction "2_2") (pintype "passive"))
      (node (ref "U5") (pin "11") (pinfunction "SS_11") (pintype "passive"))
    )
    (net (code "42") (name "Net-(U5-SW1)") (class "Default")
      (node (ref "C16") (pin "2") (pinfunction "2_2") (pintype "passive"))
      (node (ref "L2") (pin "2") (pinfunction "2_2") (pintype "passive"))
      (node (ref "U5") (pin "14") (pinfunction "SW2_14") (pintype "power_in"))
      (node (ref "U5") (pin "16") (pinfunction "SW1_16") (pintype "power_in"))
    )
    (net (code "43") (name "Net-(U5-VC)") (class "Default")
      (node (ref "R6") (pin "2") (pinfunction "2_2") (pintype "passive"))
      (node (ref "U5") (pin "8") (pinfunction "VC_8") (pintype "output"))
    )
    (net (code "44") (name "Net-(U6-5V)") (class "Default")
      (node (ref "R22") (pin "1") (pinfunction "1_1") (pintype "passive"))
      (node (ref "U6") (pin "19") (pinfunction "5V_19") (pintype "power_in"))
    )
    (net (code "45") (name "S1") (class "Default")
      (node (ref "U3") (pin "1") (pinfunction "OUT_1") (pintype "passive"))
      (node (ref "U4") (pin "1") (pinfunction "RFB_1") (pintype "output"))
    )
    (net (code "46") (name "S1_iso+") (class "Default")
      (node (ref "X1") (pin "2") (pinfunction "2_2") (pintype "passive"))
    )
    (net (code "47") (name "S1_iso-") (class "Default")
      (node (ref "U7") (pin "3") (pinfunction "+IN_3") (pintype "tri_state"))
    )
    (net (code "48") (name "TRIM") (class "Default")
      (node (ref "PS1") (pin "10") (pinfunction "TRIM_10") (pintype "passive"))
      (node (ref "R20_opt") (pin "2") (pinfunction "2_2") (pintype "passive"))
      (node (ref "R21_opt") (pin "1") (pinfunction "1_1") (pintype "passive"))
    )
    (net (code "49") (name "unconnected-(PS2-REMOTE_ON{slash}OFF-Pad3)") (class "Default")
      (node (ref "PS2") (pin "3") (pinfunction "REMOTE_ON/OFF_3") (pintype "passive"))
    )
    (net (code "50") (name "unconnected-(U1-NC-Pad6)") (class "Default")
      (node (ref "U1") (pin "6") (pinfunction "NC_6") (pintype "passive"))
    )
    (net (code "51") (name "unconnected-(U4-NC-Pad7)") (class "Default")
      (node (ref "U4") (pin "7") (pinfunction "NC_7") (pintype "passive"))
    )
    (net (code "52") (name "unconnected-(U5-NC-Pad6)") (class "Default")
      (node (ref "U5") (pin "6") (pinfunction "NC_6") (pintype "passive"))
    )
    (net (code "53") (name "unconnected-(U6-0-Pad33)") (class "Default")
      (node (ref "U6") (pin "33") (pinfunction "0_33") (pintype "bidirectional"))
    )
    (net (code "54") (name "unconnected-(U6-2-Pad34)") (class "Default")
      (node (ref "U6") (pin "34") (pinfunction "2_34") (pintype "bidirectional"))
    )
    (net (code "55") (name "unconnected-(U6-4-Pad32)") (class "Default")
      (node (ref "U6") (pin "32") (pinfunction "4_32") (pintype "bidirectional"))
    )
    (net (code "56") (name "unconnected-(U6-12-Pad13)") (class "Default")
      (node (ref "U6") (pin "13") (pinfunction "12_13") (pintype "bidirectional"))
    )
    (net (code "57") (name "unconnected-(U6-13-Pad15)") (class "Default")
      (node (ref "U6") (pin "15") (pinfunction "13_15") (pintype "bidirectional"))
    )
    (net (code "58") (name "unconnected-(U6-14-Pad12)") (class "Default")
      (node (ref "U6") (pin "12") (pinfunction "14_12") (pintype "bidirectional"))
    )
    (net (code "59") (name "unconnected-(U6-15-Pad35)") (class "Default")
      (node (ref "U6") (pin "35") (pinfunction "15_35") (pintype "bidirectional"))
    )
    (net (code "60") (name "unconnected-(U6-16-Pad31)") (class "Default")
      (node (ref "U6") (pin "31") (pinfunction "16_31") (pintype "bidirectional"))
    )
    (net (code "61") (name "unconnected-(U6-17-Pad30)") (class "Default")
      (node (ref "U6") (pin "30") (pinfunction "17_30") (pintype "bidirectional"))
    )
    (net (code "62") (name "unconnected-(U6-19-Pad27)") (class "Default")
      (node (ref "U6") (pin "27") (pinfunction "19_27") (pintype "bidirectional"))
    )
    (net (code "63") (name "unconnected-(U6-21-Pad25)") (class "Default")
      (node (ref "U6") (pin "25") (pinfunction "21_25") (pintype "bidirectional"))
    )
    (net (code "64") (name "unconnected-(U6-26-Pad10)") (class "Default")
      (node (ref "U6") (pin "10") (pinfunction "26_10") (pintype "bidirectional"))
    )
    (net (code "65") (name "unconnected-(U6-32-Pad7)") (class "Default")
      (node (ref "U6") (pin "7") (pinfunction "32_7") (pintype "bidirectional"))
    )
    (net (code "66") (name "unconnected-(U6-33-Pad8)") (class "Default")
      (node (ref "U6") (pin "8") (pinfunction "33_8") (pintype "bidirectional"))
    )
    (net (code "67") (name "unconnected-(U6-34-Pad5)") (class "Default")
      (node (ref "U6") (pin "5") (pinfunction "34_5") (pintype "bidirectional"))
    )
    (net (code "68") (name "unconnected-(U6-35-Pad6)") (class "Default")
      (node (ref "U6") (pin "6") (pinfunction "35_6") (pintype "bidirectional"))
    )
    (net (code "69") (name "unconnected-(U6-CLK-Pad38)") (class "Default")
      (node (ref "U6") (pin "38") (pinfunction "CLK_38") (pintype "bidirectional"))
    )
    (net (code "70") (name "unconnected-(U6-CMD-Pad18)") (class "Default")
      (node (ref "U6") (pin "18") (pinfunction "CMD_18") (pintype "bidirectional"))
    )
    (net (code "71") (name "unconnected-(U6-D0-Pad37)") (class "Default")
      (node (ref "U6") (pin "37") (pinfunction "D0_37") (pintype "bidirectional"))
    )
    (net (code "72") (name "unconnected-(U6-D1-Pad36)") (class "Default")
      (node (ref "U6") (pin "36") (pinfunction "D1_36") (pintype "bidirectional"))
    )
    (net (code "73") (name "unconnected-(U6-D2-Pad16)") (class "Default")
      (node (ref "U6") (pin "16") (pinfunction "D2_16") (pintype "bidirectional"))
    )
    (net (code "74") (name "unconnected-(U6-D3-Pad17)") (class "Default")
      (node (ref "U6") (pin "17") (pinfunction "D3_17") (pintype "bidirectional"))
    )
    (net (code "75") (name "unconnected-(U6-EN-Pad2)") (class "Default")
      (node (ref "U6") (pin "2") (pinfunction "EN_2") (pintype "input+no_connect"))
    )
    (net (code "76") (name "unconnected-(U6-Pad22)") (class "Default")
      (node (ref "U6") (pin "22") (pinfunction "22_22") (pintype "bidirectional"))
    )
    (net (code "77") (name "unconnected-(U6-RX-Pad24)") (class "Default")
      (node (ref "U6") (pin "24") (pinfunction "RX_24") (pintype "bidirectional"))
    )
    (net (code "78") (name "unconnected-(U6-TX-Pad23)") (class "Default")
      (node (ref "U6") (pin "23") (pinfunction "TX_23") (pintype "bidirectional"))
    )
    (net (code "79") (name "unconnected-(U6-VN-Pad4)") (class "Default")
      (node (ref "U6") (pin "4") (pinfunction "VN_4") (pintype "input+no_connect"))
    )
    (net (code "80") (name "unconnected-(U6-VP-Pad3)") (class "Default")
      (node (ref "U6") (pin "3") (pinfunction "VP_3") (pintype "input+no_connect"))
    )
    (net (code "81") (name "unconnected-(U7-Status_Flag-Pad5)") (class "Default")
      (node (ref "U7") (pin "5") (pinfunction "Status_Flag_5") (pintype "open_collector"))
    )
    (net (code "82") (name "unconnected-(U8-2Y-Pad4)") (class "Default")
      (node (ref "U8") (pin "4") (pinfunction "2Y_4") (pintype "output"))
    )
    (net (code "83") (name "unconnected-(U8-3Y-Pad10)") (class "Default")
      (node (ref "U8") (pin "10") (pinfunction "3Y_10") (pintype "output"))
    )
    (net (code "84") (name "unconnected-(U8-4Y-Pad13)") (class "Default")
      (node (ref "U8") (pin "13") (pinfunction "4Y_13") (pintype "output"))
    )
    (net (code "85") (name "unconnected-(U9-NIC-Pad3)") (class "Default")
      (node (ref "U9") (pin "3") (pinfunction "NIC_3") (pintype "passive"))
    )
    (net (code "86") (name "unconnected-(U9-NIC-Pad7)") (class "Default")
      (node (ref "U9") (pin "7") (pinfunction "NIC_7") (pintype "passive"))
    )
    (net (code "87") (name "unconnected-(U9-TP-Pad1)") (class "Default")
      (node (ref "U9") (pin "1") (pinfunction "TP_1") (pintype "passive"))
    )
    (net (code "88") (name "unconnected-(U9-TP-Pad8)") (class "Default")
      (node (ref "U9") (pin "8") (pinfunction "TP_8") (pintype "passive"))
    )
    (net (code "89") (name "unconnected-(U9-TRIM-Pad5)") (class "Default")
      (node (ref "U9") (pin "5") (pinfunction "TRIM_5") (pintype "passive"))
    )
    (net (code "90") (name "unconnected-(X1-Pad1)") (class "Default")
      (node (ref "X1") (pin "1") (pinfunction "1_1") (pintype "passive"))
    )
  )
)
